# Input_Output.net
KiCad netlist of a schematic drawn in Altium Designer
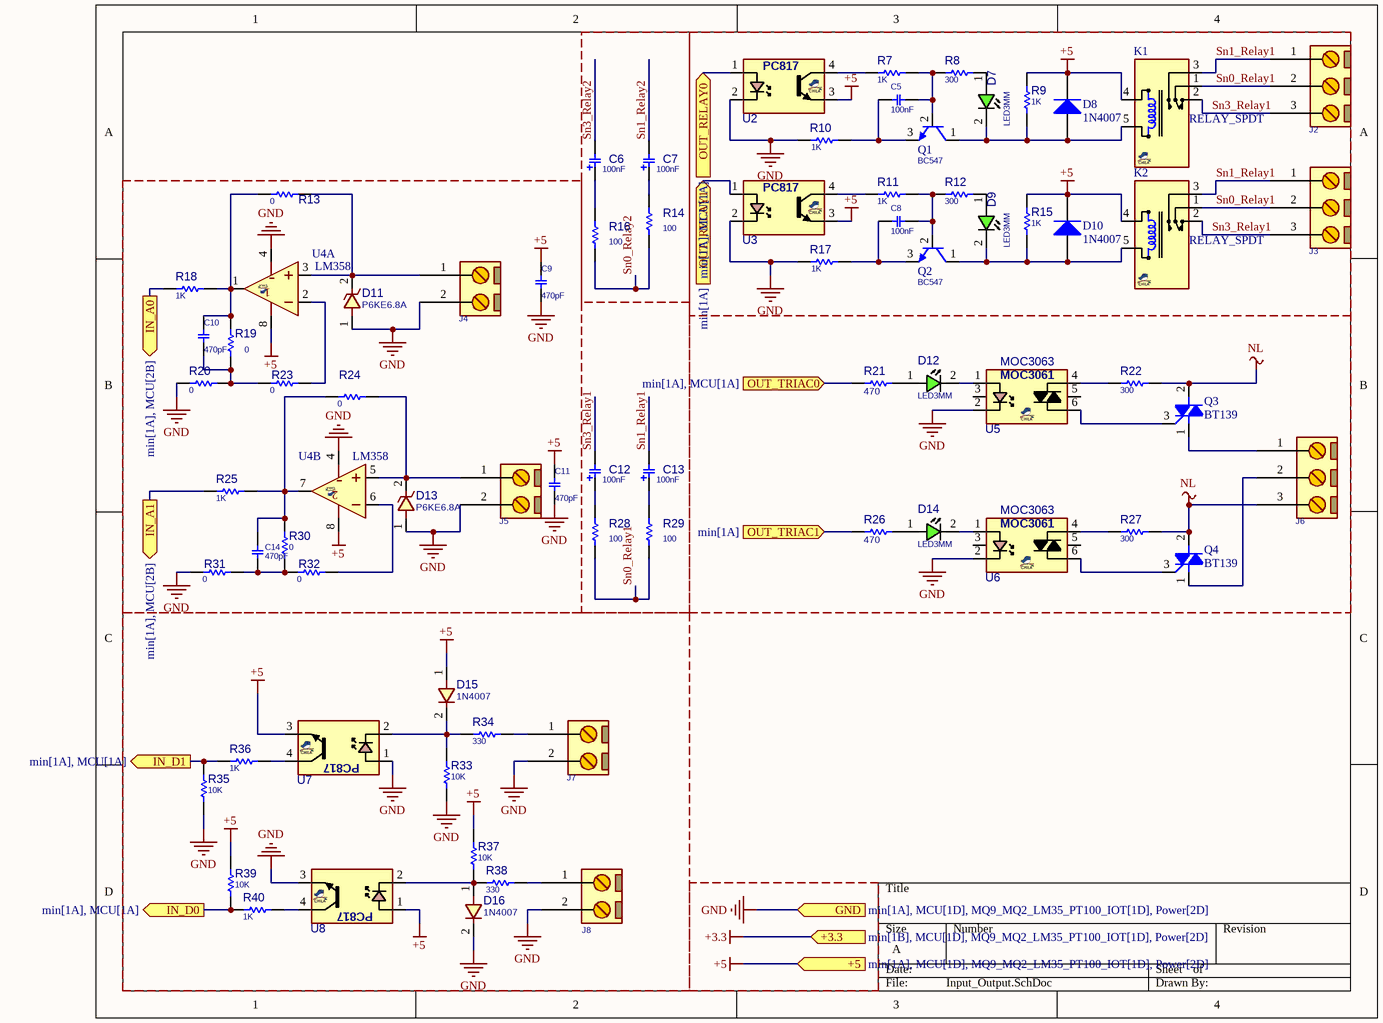
[diagram p0: Input_Output.SchDoc]

(export (version "E")
  (design (tool "Eeschema 10.0.6"))
  (components
    (comp (ref "C5")
      (value "100nF")
      (footprint "C_CERM_D3")
      (description "CAP, THD, CER MULTI LAYER,")
      (fields (field (name "MANF_P#") "MANF_PART#") (field (name "MANF") "MANF"))
      (libsource (lib "passive_thd") (part "CAP_THD_CER"))
    )
    (comp (ref "C6")
      (value "100nF")
      (footprint "C_FLM_10X5H7")
      (description "CAP, THD, FILM,")
      (fields (field (name "MANF_P#") "MANF_PART#") (field (name "MANF") "MANF"))
      (libsource (lib "passive_thd") (part "CAP_THD_FLM"))
    )
    (comp (ref "C7")
      (value "100nF")
      (footprint "C_FLM_10X5H7")
      (description "CAP, THD, FILM,")
      (fields (field (name "MANF_P#") "MANF_PART#") (field (name "MANF") "MANF"))
      (libsource (lib "passive_thd") (part "CAP_THD_FLM"))
    )
    (comp (ref "C8")
      (value "100nF")
      (footprint "C_CERM_D3")
      (description "CAP, THD, CER MULTI LAYER,")
      (fields (field (name "MANF_P#") "MANF_PART#") (field (name "MANF") "MANF"))
      (libsource (lib "passive_thd") (part "CAP_THD_CER"))
    )
    (comp (ref "C9")
      (value "470pF")
      (footprint "C_CERM_D3")
      (description "CAP, THD, CER MULTI LAYER,")
      (fields (field (name "MANF_P#") "MANF_PART#") (field (name "MANF") "MANF"))
      (libsource (lib "passive_thd") (part "CAP_THD_CER"))
    )
    (comp (ref "C10")
      (value "470pF")
      (footprint "C_CERM_D3")
      (description "CAP, THD, CER MULTI LAYER,")
      (fields (field (name "MANF_P#") "MANF_PART#") (field (name "MANF") "MANF"))
      (libsource (lib "passive_thd") (part "CAP_THD_CER"))
    )
    (comp (ref "C11")
      (value "470pF")
      (footprint "C_CERM_D3")
      (description "CAP, THD, CER MULTI LAYER,")
      (fields (field (name "MANF_P#") "MANF_PART#") (field (name "MANF") "MANF"))
      (libsource (lib "passive_thd") (part "CAP_THD_CER"))
    )
    (comp (ref "C12")
      (value "100nF")
      (footprint "C_FLM_10X5H7")
      (description "CAP, THD, FILM,")
      (fields (field (name "MANF_P#") "MANF_PART#") (field (name "MANF") "MANF"))
      (libsource (lib "passive_thd") (part "CAP_THD_FLM"))
    )
    (comp (ref "C13")
      (value "100nF")
      (footprint "C_FLM_10X5H7")
      (description "CAP, THD, FILM,")
      (fields (field (name "MANF_P#") "MANF_PART#") (field (name "MANF") "MANF"))
      (libsource (lib "passive_thd") (part "CAP_THD_FLM"))
    )
    (comp (ref "C14")
      (value "470pF")
      (footprint "C_CERM_D3")
      (description "CAP, THD, CER MULTI LAYER,")
      (fields (field (name "MANF_P#") "MANF_PART#") (field (name "MANF") "MANF"))
      (libsource (lib "passive_thd") (part "CAP_THD_CER"))
    )
    (comp (ref "D7")
      (value "LED3MM")
      (footprint "LED3MM")
      (description "LED, THD, 3MM, GREEN")
      (fields (field (name "MANF") "MANF") (field (name "MANF_P#") "MANF_PART#"))
      (libsource (lib "led(diode)") (part "LED_THD_3MM"))
    )
    (comp (ref "D8")
      (value "1N4007")
      (footprint "Diode 1n4007")
      (description "Diode")
      (fields (field (name "PUBLISHER") "Altium Limited"))
      (libsource (lib "Altium (2)") (part "Diode"))
    )
    (comp (ref "D9")
      (value "LED3MM")
      (footprint "LED3MM")
      (description "LED, THD, 3MM, GREEN")
      (fields (field (name "MANF") "MANF") (field (name "MANF_P#") "MANF_PART#"))
      (libsource (lib "led(diode)") (part "LED_THD_3MM"))
    )
    (comp (ref "D10")
      (value "1N4007")
      (footprint "Diode 1n4007")
      (description "Diode")
      (fields (field (name "PUBLISHER") "Altium Limited"))
      (libsource (lib "Altium (2)") (part "Diode"))
    )
    (comp (ref "D11")
      (value "P6KE6.8A")
      (footprint "D_AX04_DO41")
      (description "DIODE, ZENER, 0.2W, 15V")
      (fields (field (name "MANF") "Diodes") (field (name "MANF_P#") "ZENER15V"))
      (libsource (lib "diode") (part "DIODE_THD_ZENER"))
    )
    (comp (ref "D12")
      (value "LED3MM")
      (footprint "LED3MM")
      (description "LED, THD, 3MM, GREEN")
      (fields (field (name "MANF") "MANF") (field (name "MANF_P#") "MANF_PART#"))
      (libsource (lib "led(diode)") (part "LED_THD_3MM"))
    )
    (comp (ref "D13")
      (value "P6KE6.8A")
      (footprint "D_AX04_DO41")
      (description "DIODE, ZENER, 0.2W, 15V")
      (fields (field (name "MANF") "Diodes") (field (name "MANF_P#") "ZENER15V"))
      (libsource (lib "diode") (part "DIODE_THD_ZENER"))
    )
    (comp (ref "D14")
      (value "LED3MM")
      (footprint "LED3MM")
      (description "LED, THD, 3MM, GREEN")
      (fields (field (name "MANF") "MANF") (field (name "MANF_P#") "MANF_PART#"))
      (libsource (lib "led(diode)") (part "LED_THD_3MM"))
    )
    (comp (ref "D15")
      (value "1N4007")
      (footprint "D_AX04_DO41")
      (description "DIODE, GENERAL PURPOSE, 1000V/1A")
      (fields (field (name "MANF") "Diodes"))
      (libsource (lib "diode") (part "DIODE_THD_1N4007"))
    )
    (comp (ref "D16")
      (value "1N4007")
      (footprint "D_AX04_DO41")
      (description "DIODE, GENERAL PURPOSE, 1000V/1A")
      (fields (field (name "MANF") "Diodes"))
      (libsource (lib "diode") (part "DIODE_THD_1N4007"))
    )
    (comp (ref "J2")
      (value "CONN_GMSTB3")
      (footprint "GMSTB762_3")
      (description "CONN, PHOENIX MSTB, 5-G, 5.08mm pitch")
      (fields (field (name "MANF_P#") "GMSTB 2,5/3-G-7,62"))
      (libsource (lib "conn_terminalB") (part "CONN_GMSTB762_3"))
    )
    (comp (ref "J3")
      (value "CONN_GMSTB3")
      (footprint "GMSTB762_3")
      (description "CONN, PHOENIX MSTB, 5-G, 5.08mm pitch")
      (fields (field (name "MANF_P#") "GMSTB 2,5/3-G-7,62"))
      (libsource (lib "conn_terminalB") (part "CONN_GMSTB762_3"))
    )
    (comp (ref "J4")
      (value "CONN_GMSTB2")
      (footprint "GMSTB762_2")
      (description "CONN, PHOENIX GMSTB, 7.62mm pitch")
      (fields (field (name "MANF_P#") "GMSTB 2,5/2-G-7,62"))
      (libsource (lib "conn_terminalB") (part "CONN_GMSTB762_2"))
    )
    (comp (ref "J5")
      (value "CONN_GMSTB2")
      (footprint "GMSTB762_2")
      (description "CONN, PHOENIX GMSTB, 7.62mm pitch")
      (fields (field (name "MANF_P#") "GMSTB 2,5/2-G-7,62"))
      (libsource (lib "conn_terminalB") (part "CONN_GMSTB762_2"))
    )
    (comp (ref "J6")
      (value "CONN_GMSTB3")
      (footprint "GMSTB762_3")
      (description "CONN, PHOENIX MSTB, 5-G, 5.08mm pitch")
      (fields (field (name "MANF_P#") "GMSTB 2,5/3-G-7,62"))
      (libsource (lib "conn_terminalB") (part "CONN_GMSTB762_3"))
    )
    (comp (ref "J7")
      (value "CONN_GMSTB2")
      (footprint "GMSTB762_2")
      (description "CONN, PHOENIX GMSTB, 7.62mm pitch")
      (fields (field (name "MANF_P#") "GMSTB 2,5/2-G-7,62"))
      (libsource (lib "conn_terminalB") (part "CONN_GMSTB762_2"))
    )
    (comp (ref "J8")
      (value "CONN_GMSTB2")
      (footprint "GMSTB762_2")
      (description "CONN, PHOENIX GMSTB, 7.62mm pitch")
      (fields (field (name "MANF_P#") "GMSTB 2,5/2-G-7,62"))
      (libsource (lib "conn_terminalB") (part "CONN_GMSTB762_2"))
    )
    (comp (ref "K1")
      (value "RELAY_SPDT")
      (footprint "REL_SPDT_5_2216")
      (description "Relay, SPDT, 5P, 19X15mm, 240VAC/7A")
      (fields (field (name "MANF") "TIANBO") (field (name "MANF_P#") "HJR-3FF--12VDC"))
      (libsource (lib "relay") (part "RELAY_SPDT_5_2216_HJR-3FF"))
    )
    (comp (ref "K2")
      (value "RELAY_SPDT")
      (footprint "REL_SPDT_5_2216")
      (description "Relay, SPDT, 5P, 19X15mm, 240VAC/7A")
      (fields (field (name "MANF") "TIANBO") (field (name "MANF_P#") "HJR-3FF--12VDC"))
      (libsource (lib "relay") (part "RELAY_SPDT_5_2216_HJR-3FF"))
    )
    (comp (ref "Q1")
      (value "BC547")
      (footprint "TO92_3")
      (description "BJT, NPN, 45v, 0.1A, THD, TO92")
      (fields (field (name "MANF") "FAIRCHILD"))
      (libsource (lib "transistor_bjt") (part "NPN_BC547_TO92"))
    )
    (comp (ref "Q2")
      (value "BC547")
      (footprint "TO92_3")
      (description "BJT, NPN, 45v, 0.1A, THD, TO92")
      (fields (field (name "MANF") "FAIRCHILD"))
      (libsource (lib "transistor_bjt") (part "NPN_BC547_TO92"))
    )
    (comp (ref "Q3")
      (value "BT139")
      (footprint "TO220_3")
      (description "Triac, 600V, 4A, TO-220, Silicon Bidirectional Thyristor")
      (libsource (lib "triac_diac") (part "TRIAC"))
    )
    (comp (ref "Q4")
      (value "BT139")
      (footprint "TO220_3")
      (description "Triac, 600V, 4A, TO-220, Silicon Bidirectional Thyristor")
      (libsource (lib "triac_diac") (part "TRIAC"))
    )
    (comp (ref "R7")
      (value "1K")
      (footprint "R025W_AX_VER")
      (description "RESISTOR, THD")
      (fields (field (name "MANF_P#") "RK73H1ETTP4701F") (field (name "MANF") "KOA SPEER"))
      (libsource (lib "passive_thd") (part "RES_THD"))
    )
    (comp (ref "R8")
      (value "300")
      (footprint "R025W_AX_VER")
      (description "RESISTOR, THD")
      (fields (field (name "MANF_P#") "RK73H1ETTP4701F") (field (name "MANF") "KOA SPEER"))
      (libsource (lib "passive_thd") (part "RES_THD"))
    )
    (comp (ref "R9")
      (value "1K")
      (footprint "R025W_AX_VER")
      (description "RESISTOR, THD")
      (fields (field (name "MANF_P#") "RK73H1ETTP4701F") (field (name "MANF") "KOA SPEER"))
      (libsource (lib "passive_thd") (part "RES_THD"))
    )
    (comp (ref "R10")
      (value "1K")
      (footprint "R025W_AX_VER")
      (description "RESISTOR, THD")
      (fields (field (name "MANF_P#") "RK73H1ETTP4701F") (field (name "MANF") "KOA SPEER"))
      (libsource (lib "passive_thd") (part "RES_THD"))
    )
    (comp (ref "R11")
      (value "1K")
      (footprint "R025W_AX_VER")
      (description "RESISTOR, THD")
      (fields (field (name "MANF_P#") "RK73H1ETTP4701F") (field (name "MANF") "KOA SPEER"))
      (libsource (lib "passive_thd") (part "RES_THD"))
    )
    (comp (ref "R12")
      (value "300")
      (footprint "R025W_AX_VER")
      (description "RESISTOR, THD")
      (fields (field (name "MANF_P#") "RK73H1ETTP4701F") (field (name "MANF") "KOA SPEER"))
      (libsource (lib "passive_thd") (part "RES_THD"))
    )
    (comp (ref "R13")
      (value "0")
      (footprint "R0125W_AX03")
      (description "RESISTOR, THD")
      (fields (field (name "MANF_P#") "RK73H1ETTP4701F") (field (name "MANF") "KOA SPEER"))
      (libsource (lib "passive_thd") (part "RES_THD"))
    )
    (comp (ref "R14")
      (value "100")
      (footprint "R025W_AX_VER")
      (description "RESISTOR, THD")
      (fields (field (name "MANF_P#") "RK73H1ETTP4701F") (field (name "MANF") "KOA SPEER"))
      (libsource (lib "passive_thd") (part "RES_THD"))
    )
    (comp (ref "R15")
      (value "1K")
      (footprint "R025W_AX_VER")
      (description "RESISTOR, THD")
      (fields (field (name "MANF_P#") "RK73H1ETTP4701F") (field (name "MANF") "KOA SPEER"))
      (libsource (lib "passive_thd") (part "RES_THD"))
    )
    (comp (ref "R16")
      (value "100")
      (footprint "R025W_AX_VER")
      (description "RESISTOR, THD")
      (fields (field (name "MANF_P#") "RK73H1ETTP4701F") (field (name "MANF") "KOA SPEER"))
      (libsource (lib "passive_thd") (part "RES_THD"))
    )
    (comp (ref "R17")
      (value "1K")
      (footprint "R025W_AX_VER")
      (description "RESISTOR, THD")
      (fields (field (name "MANF_P#") "RK73H1ETTP4701F") (field (name "MANF") "KOA SPEER"))
      (libsource (lib "passive_thd") (part "RES_THD"))
    )
    (comp (ref "R18")
      (value "1K")
      (footprint "R0125W_AX03")
      (description "RESISTOR, THD")
      (fields (field (name "MANF_P#") "RK73H1ETTP4701F") (field (name "MANF") "KOA SPEER"))
      (libsource (lib "passive_thd") (part "RES_THD"))
    )
    (comp (ref "R19")
      (value "0")
      (footprint "R0125W_AX03")
      (description "RESISTOR, THD")
      (fields (field (name "MANF_P#") "RK73H1ETTP4701F") (field (name "MANF") "KOA SPEER"))
      (libsource (lib "passive_thd") (part "RES_THD"))
    )
    (comp (ref "R20")
      (value "0")
      (footprint "R0125W_AX03")
      (description "RESISTOR, THD")
      (fields (field (name "MANF_P#") "RK73H1ETTP4701F") (field (name "MANF") "KOA SPEER"))
      (libsource (lib "passive_thd") (part "RES_THD"))
    )
    (comp (ref "R21")
      (value "470")
      (footprint "R1206")
      (description "RESISTOR, SMD")
      (libsource (lib "passive_smd") (part "RES_SMD"))
    )
    (comp (ref "R22")
      (value "300")
      (footprint "R025W_AX_VER")
      (description "RESISTOR, THD")
      (fields (field (name "MANF_P#") "RK73H1ETTP4701F") (field (name "MANF") "KOA SPEER"))
      (libsource (lib "passive_thd") (part "RES_THD"))
    )
    (comp (ref "R23")
      (value "0")
      (footprint "R0125W_AX03")
      (description "RESISTOR, THD")
      (fields (field (name "MANF_P#") "RK73H1ETTP4701F") (field (name "MANF") "KOA SPEER"))
      (libsource (lib "passive_thd") (part "RES_THD"))
    )
    (comp (ref "R24")
      (value "0")
      (footprint "R0125W_AX03")
      (description "RESISTOR, THD")
      (fields (field (name "MANF_P#") "RK73H1ETTP4701F") (field (name "MANF") "KOA SPEER"))
      (libsource (lib "passive_thd") (part "RES_THD"))
    )
    (comp (ref "R25")
      (value "1K")
      (footprint "R0125W_AX03")
      (description "RESISTOR, THD")
      (fields (field (name "MANF_P#") "RK73H1ETTP4701F") (field (name "MANF") "KOA SPEER"))
      (libsource (lib "passive_thd") (part "RES_THD"))
    )
    (comp (ref "R26")
      (value "470")
      (footprint "R1206")
      (description "RESISTOR, SMD")
      (libsource (lib "passive_smd") (part "RES_SMD"))
    )
    (comp (ref "R27")
      (value "300")
      (footprint "R025W_AX_VER")
      (description "RESISTOR, THD")
      (fields (field (name "MANF_P#") "RK73H1ETTP4701F") (field (name "MANF") "KOA SPEER"))
      (libsource (lib "passive_thd") (part "RES_THD"))
    )
    (comp (ref "R28")
      (value "100")
      (footprint "R025W_AX_VER")
      (description "RESISTOR, THD")
      (fields (field (name "MANF_P#") "RK73H1ETTP4701F") (field (name "MANF") "KOA SPEER"))
      (libsource (lib "passive_thd") (part "RES_THD"))
    )
    (comp (ref "R29")
      (value "100")
      (footprint "R025W_AX_VER")
      (description "RESISTOR, THD")
      (fields (field (name "MANF_P#") "RK73H1ETTP4701F") (field (name "MANF") "KOA SPEER"))
      (libsource (lib "passive_thd") (part "RES_THD"))
    )
    (comp (ref "R30")
      (value "0")
      (footprint "R0125W_AX03")
      (description "RESISTOR, THD")
      (fields (field (name "MANF_P#") "RK73H1ETTP4701F") (field (name "MANF") "KOA SPEER"))
      (libsource (lib "passive_thd") (part "RES_THD"))
    )
    (comp (ref "R31")
      (value "0")
      (footprint "R0125W_AX03")
      (description "RESISTOR, THD")
      (fields (field (name "MANF_P#") "RK73H1ETTP4701F") (field (name "MANF") "KOA SPEER"))
      (libsource (lib "passive_thd") (part "RES_THD"))
    )
    (comp (ref "R32")
      (value "0")
      (footprint "R0125W_AX03")
      (description "RESISTOR, THD")
      (fields (field (name "MANF_P#") "RK73H1ETTP4701F") (field (name "MANF") "KOA SPEER"))
      (libsource (lib "passive_thd") (part "RES_THD"))
    )
    (comp (ref "R33")
      (value "10K")
      (footprint "R0125W_AX03")
      (description "RESISTOR, THD")
      (fields (field (name "MANF_P#") "RK73H1ETTP4701F") (field (name "MANF") "KOA SPEER"))
      (libsource (lib "passive_thd") (part "RES_THD"))
    )
    (comp (ref "R34")
      (value "330")
      (footprint "R0125W_AX03")
      (description "RESISTOR, THD")
      (fields (field (name "MANF_P#") "RK73H1ETTP4701F") (field (name "MANF") "KOA SPEER"))
      (libsource (lib "passive_thd") (part "RES_THD"))
    )
    (comp (ref "R35")
      (value "10K")
      (footprint "R0125W_AX03")
      (description "RESISTOR, THD")
      (fields (field (name "MANF_P#") "RK73H1ETTP4701F") (field (name "MANF") "KOA SPEER"))
      (libsource (lib "passive_thd") (part "RES_THD"))
    )
    (comp (ref "R36")
      (value "1K")
      (footprint "R0125W_AX03")
      (description "RESISTOR, THD")
      (fields (field (name "MANF_P#") "RK73H1ETTP4701F") (field (name "MANF") "KOA SPEER"))
      (libsource (lib "passive_thd") (part "RES_THD"))
    )
    (comp (ref "R37")
      (value "10K")
      (footprint "R0125W_AX03")
      (description "RESISTOR, THD")
      (fields (field (name "MANF_P#") "RK73H1ETTP4701F") (field (name "MANF") "KOA SPEER"))
      (libsource (lib "passive_thd") (part "RES_THD"))
    )
    (comp (ref "R38")
      (value "330")
      (footprint "R0125W_AX03")
      (description "RESISTOR, THD")
      (fields (field (name "MANF_P#") "RK73H1ETTP4701F") (field (name "MANF") "KOA SPEER"))
      (libsource (lib "passive_thd") (part "RES_THD"))
    )
    (comp (ref "R39")
      (value "10K")
      (footprint "R0125W_AX03")
      (description "RESISTOR, THD")
      (fields (field (name "MANF_P#") "RK73H1ETTP4701F") (field (name "MANF") "KOA SPEER"))
      (libsource (lib "passive_thd") (part "RES_THD"))
    )
    (comp (ref "R40")
      (value "1K")
      (footprint "R0125W_AX03")
      (description "RESISTOR, THD")
      (fields (field (name "MANF_P#") "RK73H1ETTP4701F") (field (name "MANF") "KOA SPEER"))
      (libsource (lib "passive_thd") (part "RES_THD"))
    )
    (comp (ref "U2")
      (value "PC817")
      (footprint "DIP_4")
      (description "OPTOCOUPLER, TRANSISTOR, 4PIN")
      (fields (field (name "MANF") "SHARP"))
      (libsource (lib "") (part "OPTC_TR4P_PC817_1"))
    )
    (comp (ref "U3")
      (value "PC817")
      (footprint "DIP_4")
      (description "OPTOCOUPLER, TRANSISTOR, 4PIN")
      (fields (field (name "MANF") "SHARP"))
      (libsource (lib "") (part "OPTC_TR4P_PC817_1"))
    )
    (comp (ref "U4")
      (value "LM358")
      (footprint "DIP_8")
      (description "AMP, Dual, Low-Power")
      (fields (field (name "MANF") "Texas Instruments, Fairchild") (field (name "MANF_P#") "LM358AN"))
      (libsource (lib "amp") (part "LM358_DIP8"))
    )
    (comp (ref "U5")
      (value "MOC3063")
      (footprint "DIP_6")
      (description "OPTOTRIAC, 600v/1A, 6v In")
      (fields (field (name "MANF_P#") "MOC3061"))
      (libsource (lib "optocoupler") (part "OPT_TRIAC6P_MOC3061"))
    )
    (comp (ref "U6")
      (value "MOC3063")
      (footprint "DIP_6")
      (description "OPTOTRIAC, 600v/1A, 6v In")
      (fields (field (name "MANF_P#") "MOC3061"))
      (libsource (lib "optocoupler") (part "OPT_TRIAC6P_MOC3061"))
    )
    (comp (ref "U7")
      (value "PC817")
      (footprint "DIP_4")
      (description "OPTOCOUPLER, TRANSISTOR, 4PIN")
      (fields (field (name "MANF") "SHARP"))
      (libsource (lib "optocoupler") (part "OPTC_TR4P_PC817"))
    )
    (comp (ref "U8")
      (value "PC817")
      (footprint "DIP_4")
      (description "OPTOCOUPLER, TRANSISTOR, 4PIN")
      (fields (field (name "MANF") "SHARP"))
      (libsource (lib "optocoupler") (part "OPTC_TR4P_PC817"))
    )
  )
  (nets
    (net (code "2") (name "+5") (class "Default")
      (node (ref "C11") (pin "2") (pinfunction "2_2") (pintype "passive"))
      (node (ref "C9") (pin "2") (pinfunction "2_2") (pintype "passive"))
      (node (ref "D10") (pin "2") (pinfunction "K_2") (pintype "passive"))
      (node (ref "D15") (pin "1") (pinfunction "1_1") (pintype "passive"))
      (node (ref "D8") (pin "2") (pinfunction "K_2") (pintype "passive"))
      (node (ref "K1") (pin "4") (pinfunction "T1_4") (pintype "passive"))
      (node (ref "K2") (pin "4") (pinfunction "T1_4") (pintype "passive"))
      (node (ref "R15") (pin "1") (pinfunction "1_1") (pintype "passive"))
      (node (ref "R37") (pin "2") (pinfunction "2_2") (pintype "passive"))
      (node (ref "R39") (pin "2") (pinfunction "2_2") (pintype "passive"))
      (node (ref "R9") (pin "1") (pinfunction "1_1") (pintype "passive"))
      (node (ref "U2") (pin "3") (pinfunction "E_3") (pintype "passive"))
      (node (ref "U3") (pin "3") (pinfunction "E_3") (pintype "passive"))
      (node (ref "U4") (pin "8") (pinfunction "V+_8") (pintype "passive"))
      (node (ref "U7") (pin "3") (pinfunction "E_3") (pintype "passive"))
      (node (ref "U8") (pin "1") (pinfunction "A_1") (pintype "passive"))
    )
    (net (code "3") (name "/IN_A0") (class "Default")
      (node (ref "R18") (pin "2") (pinfunction "2_2") (pintype "passive"))
    )
    (net (code "4") (name "/IN_A1") (class "Default")
      (node (ref "R25") (pin "2") (pinfunction "2_2") (pintype "passive"))
    )
    (net (code "5") (name "/IN_D0") (class "Default")
      (node (ref "R39") (pin "1") (pinfunction "1_1") (pintype "passive"))
      (node (ref "R40") (pin "1") (pinfunction "1_1") (pintype "passive"))
    )
    (net (code "6") (name "/IN_D1") (class "Default")
      (node (ref "R35") (pin "1") (pinfunction "1_1") (pintype "passive"))
      (node (ref "R36") (pin "1") (pinfunction "1_1") (pintype "passive"))
    )
    (net (code "7") (name "/OUT_RELAY0") (class "Default")
      (node (ref "U2") (pin "1") (pinfunction "A_1") (pintype "passive"))
    )
    (net (code "8") (name "/OUT_RELAY1") (class "Default")
      (node (ref "U3") (pin "1") (pinfunction "A_1") (pintype "passive"))
    )
    (net (code "9") (name "/OUT_TRIAC0") (class "Default")
      (node (ref "R21") (pin "2") (pinfunction "2_2") (pintype "passive"))
    )
    (net (code "10") (name "/OUT_TRIAC1") (class "Default")
      (node (ref "R26") (pin "2") (pinfunction "2_2") (pintype "passive"))
    )
    (net (code "11") (name "/Sn0_Relay1") (class "Default")
      (node (ref "J2") (pin "2") (pinfunction "2_2") (pintype "passive"))
      (node (ref "J3") (pin "2") (pinfunction "2_2") (pintype "passive"))
      (node (ref "K1") (pin "1") (pinfunction "COM_1") (pintype "passive"))
      (node (ref "K2") (pin "1") (pinfunction "COM_1") (pintype "passive"))
      (node (ref "R28") (pin "1") (pinfunction "1_1") (pintype "passive"))
      (node (ref "R29") (pin "1") (pinfunction "1_1") (pintype "passive"))
    )
    (net (code "12") (name "/Sn0_Relay2") (class "Default")
      (node (ref "R14") (pin "1") (pinfunction "1_1") (pintype "passive"))
      (node (ref "R16") (pin "1") (pinfunction "1_1") (pintype "passive"))
    )
    (net (code "13") (name "/Sn1_Relay1") (class "Default")
      (node (ref "C13") (pin "2") (pinfunction "2_2") (pintype "passive"))
      (node (ref "J2") (pin "1") (pinfunction "1_1") (pintype "passive"))
      (node (ref "J3") (pin "1") (pinfunction "1_1") (pintype "passive"))
      (node (ref "K1") (pin "3") (pinfunction "NO_3") (pintype "passive"))
      (node (ref "K2") (pin "3") (pinfunction "NO_3") (pintype "passive"))
    )
    (net (code "14") (name "/Sn1_Relay2") (class "Default")
      (node (ref "C7") (pin "2") (pinfunction "2_2") (pintype "passive"))
    )
    (net (code "15") (name "/Sn3_Relay1") (class "Default")
      (node (ref "C12") (pin "2") (pinfunction "2_2") (pintype "passive"))
      (node (ref "J2") (pin "3") (pinfunction "3_3") (pintype "passive"))
      (node (ref "J3") (pin "3") (pinfunction "3_3") (pintype "passive"))
      (node (ref "K1") (pin "2") (pinfunction "NC_2") (pintype "passive"))
      (node (ref "K2") (pin "2") (pinfunction "NC_2") (pintype "passive"))
    )
    (net (code "16") (name "/Sn3_Relay2") (class "Default")
      (node (ref "C6") (pin "2") (pinfunction "2_2") (pintype "passive"))
    )
    (net (code "17") (name "GND") (class "Default")
      (node (ref "C11") (pin "1") (pinfunction "1_1") (pintype "passive"))
      (node (ref "C9") (pin "1") (pinfunction "1_1") (pintype "passive"))
      (node (ref "D11") (pin "1") (pinfunction "1_1") (pintype "passive"))
      (node (ref "D13") (pin "1") (pinfunction "1_1") (pintype "passive"))
      (node (ref "D16") (pin "2") (pinfunction "2_2") (pintype "passive"))
      (node (ref "J4") (pin "2") (pinfunction "2_2") (pintype "passive"))
      (node (ref "J5") (pin "2") (pinfunction "2_2") (pintype "passive"))
      (node (ref "J7") (pin "2") (pinfunction "2_2") (pintype "passive"))
      (node (ref "J8") (pin "2") (pinfunction "2_2") (pintype "passive"))
      (node (ref "R10") (pin "2") (pinfunction "2_2") (pintype "passive"))
      (node (ref "R17") (pin "2") (pinfunction "2_2") (pintype "passive"))
      (node (ref "R20") (pin "2") (pinfunction "2_2") (pintype "passive"))
      (node (ref "R31") (pin "2") (pinfunction "2_2") (pintype "passive"))
      (node (ref "R33") (pin "2") (pinfunction "2_2") (pintype "passive"))
      (node (ref "R35") (pin "2") (pinfunction "2_2") (pintype "passive"))
      (node (ref "U2") (pin "2") (pinfunction "K_2") (pintype "passive"))
      (node (ref "U3") (pin "2") (pinfunction "K_2") (pintype "passive"))
      (node (ref "U4") (pin "4") (pinfunction "V-_4") (pintype "passive"))
      (node (ref "U5") (pin "2") (pinfunction "K_2") (pintype "passive"))
      (node (ref "U6") (pin "2") (pinfunction "K_2") (pintype "passive"))
      (node (ref "U7") (pin "1") (pinfunction "A_1") (pintype "passive"))
      (node (ref "U8") (pin "3") (pinfunction "E_3") (pintype "passive"))
    )
    (net (code "18") (name "NL") (class "Default")
      (node (ref "J6") (pin "3") (pinfunction "3_3") (pintype "passive"))
      (node (ref "Q3") (pin "2") (pinfunction "T2_2") (pintype "passive"))
      (node (ref "Q4") (pin "2") (pinfunction "T2_2") (pintype "passive"))
      (node (ref "R22") (pin "2") (pinfunction "2_2") (pintype "passive"))
      (node (ref "R27") (pin "2") (pinfunction "2_2") (pintype "passive"))
    )
    (net (code "19") (name "Net-(C6-Pad1)") (class "Default")
      (node (ref "C6") (pin "1") (pinfunction "1_1") (pintype "passive"))
      (node (ref "R16") (pin "2") (pinfunction "2_2") (pintype "passive"))
    )
    (net (code "20") (name "Net-(C7-Pad1)") (class "Default")
      (node (ref "C7") (pin "1") (pinfunction "1_1") (pintype "passive"))
      (node (ref "R14") (pin "2") (pinfunction "2_2") (pintype "passive"))
    )
    (net (code "21") (name "Net-(C10-Pad1)") (class "Default")
      (node (ref "C10") (pin "1") (pinfunction "1_1") (pintype "passive"))
      (node (ref "R19") (pin "2") (pinfunction "2_2") (pintype "passive"))
      (node (ref "R20") (pin "1") (pinfunction "1_1") (pintype "passive"))
      (node (ref "R23") (pin "1") (pinfunction "1_1") (pintype "passive"))
    )
    (net (code "22") (name "Net-(C12-Pad1)") (class "Default")
      (node (ref "C12") (pin "1") (pinfunction "1_1") (pintype "passive"))
      (node (ref "R28") (pin "2") (pinfunction "2_2") (pintype "passive"))
    )
    (net (code "23") (name "Net-(C13-Pad1)") (class "Default")
      (node (ref "C13") (pin "1") (pinfunction "1_1") (pintype "passive"))
      (node (ref "R29") (pin "2") (pinfunction "2_2") (pintype "passive"))
    )
    (net (code "24") (name "Net-(C14-Pad1)") (class "Default")
      (node (ref "C14") (pin "1") (pinfunction "1_1") (pintype "passive"))
      (node (ref "R30") (pin "1") (pinfunction "1_1") (pintype "passive"))
      (node (ref "R31") (pin "1") (pinfunction "1_1") (pintype "passive"))
      (node (ref "R32") (pin "1") (pinfunction "1_1") (pintype "passive"))
    )
    (net (code "25") (name "Net-(D7-ANODE)") (class "Default")
      (node (ref "D7") (pin "1") (pinfunction "ANODE_1") (pintype "passive"))
      (node (ref "R8") (pin "2") (pinfunction "2_2") (pintype "passive"))
    )
    (net (code "26") (name "Net-(D7-CATHODE)") (class "Default")
      (node (ref "D7") (pin "2") (pinfunction "CATHODE_2") (pintype "passive"))
      (node (ref "D8") (pin "1") (pinfunction "A_1") (pintype "passive"))
      (node (ref "K1") (pin "5") (pinfunction "T2_5") (pintype "passive"))
      (node (ref "Q1") (pin "1") (pinfunction "C_1") (pintype "passive"))
      (node (ref "R9") (pin "2") (pinfunction "2_2") (pintype "passive"))
    )
    (net (code "27") (name "Net-(D9-ANODE)") (class "Default")
      (node (ref "D9") (pin "1") (pinfunction "ANODE_1") (pintype "passive"))
      (node (ref "R12") (pin "2") (pinfunction "2_2") (pintype "passive"))
    )
    (net (code "28") (name "Net-(D10-A)") (class "Default")
      (node (ref "D10") (pin "1") (pinfunction "A_1") (pintype "passive"))
      (node (ref "D9") (pin "2") (pinfunction "CATHODE_2") (pintype "passive"))
      (node (ref "K2") (pin "5") (pinfunction "T2_5") (pintype "passive"))
      (node (ref "Q2") (pin "1") (pinfunction "C_1") (pintype "passive"))
      (node (ref "R15") (pin "2") (pinfunction "2_2") (pintype "passive"))
    )
    (net (code "29") (name "Net-(D12-ANODE)") (class "Default")
      (node (ref "D12") (pin "1") (pinfunction "ANODE_1") (pintype "passive"))
      (node (ref "R21") (pin "1") (pinfunction "1_1") (pintype "passive"))
    )
    (net (code "30") (name "Net-(D12-CATHODE)") (class "Default")
      (node (ref "D12") (pin "2") (pinfunction "CATHODE_2") (pintype "passive"))
      (node (ref "U5") (pin "1") (pinfunction "A_1") (pintype "passive"))
    )
    (net (code "31") (name "Net-(D14-ANODE)") (class "Default")
      (node (ref "D14") (pin "1") (pinfunction "ANODE_1") (pintype "passive"))
      (node (ref "R26") (pin "1") (pinfunction "1_1") (pintype "passive"))
    )
    (net (code "32") (name "Net-(D14-CATHODE)") (class "Default")
      (node (ref "D14") (pin "2") (pinfunction "CATHODE_2") (pintype "passive"))
      (node (ref "U6") (pin "1") (pinfunction "A_1") (pintype "passive"))
    )
    (net (code "33") (name "Net-(J7-Pad1)") (class "Default")
      (node (ref "J7") (pin "1") (pinfunction "1_1") (pintype "passive"))
      (node (ref "R34") (pin "2") (pinfunction "2_2") (pintype "passive"))
    )
    (net (code "34") (name "Net-(J8-Pad1)") (class "Default")
      (node (ref "J8") (pin "1") (pinfunction "1_1") (pintype "passive"))
      (node (ref "R38") (pin "2") (pinfunction "2_2") (pintype "passive"))
    )
    (net (code "35") (name "Net-(Q1-B)") (class "Default")
      (node (ref "C5") (pin "1") (pinfunction "1_1") (pintype "passive"))
      (node (ref "Q1") (pin "2") (pinfunction "B_2") (pintype "passive"))
      (node (ref "R7") (pin "1") (pinfunction "1_1") (pintype "passive"))
      (node (ref "R8") (pin "1") (pinfunction "1_1") (pintype "passive"))
    )
    (net (code "36") (name "Net-(Q1-E)") (class "Default")
      (node (ref "C5") (pin "2") (pinfunction "2_2") (pintype "passive"))
      (node (ref "Q1") (pin "3") (pinfunction "E_3") (pintype "passive"))
      (node (ref "R10") (pin "1") (pinfunction "1_1") (pintype "passive"))
    )
    (net (code "37") (name "Net-(Q2-B)") (class "Default")
      (node (ref "C8") (pin "1") (pinfunction "1_1") (pintype "passive"))
      (node (ref "Q2") (pin "2") (pinfunction "B_2") (pintype "passive"))
      (node (ref "R11") (pin "1") (pinfunction "1_1") (pintype "passive"))
      (node (ref "R12") (pin "1") (pinfunction "1_1") (pintype "passive"))
    )
    (net (code "38") (name "Net-(Q2-E)") (class "Default")
      (node (ref "C8") (pin "2") (pinfunction "2_2") (pintype "passive"))
      (node (ref "Q2") (pin "3") (pinfunction "E_3") (pintype "passive"))
      (node (ref "R17") (pin "1") (pinfunction "1_1") (pintype "passive"))
    )
    (net (code "39") (name "Net-(Q3-G)") (class "Default")
      (node (ref "Q3") (pin "3") (pinfunction "G_3") (pintype "passive"))
      (node (ref "U5") (pin "6") (pinfunction "A/K_6") (pintype "passive"))
    )
    (net (code "40") (name "Net-(Q3-T1)") (class "Default")
      (node (ref "J6") (pin "1") (pinfunction "1_1") (pintype "passive"))
      (node (ref "Q3") (pin "1") (pinfunction "T1_1") (pintype "passive"))
    )
    (net (code "41") (name "Net-(Q4-G)") (class "Default")
      (node (ref "Q4") (pin "3") (pinfunction "G_3") (pintype "passive"))
      (node (ref "U6") (pin "6") (pinfunction "A/K_6") (pintype "passive"))
    )
    (net (code "42") (name "Net-(Q4-T1)") (class "Default")
      (node (ref "J6") (pin "2") (pinfunction "2_2") (pintype "passive"))
      (node (ref "Q4") (pin "1") (pinfunction "T1_1") (pintype "passive"))
    )
    (net (code "43") (name "Net-(R22-Pad1)") (class "Default")
      (node (ref "R22") (pin "1") (pinfunction "1_1") (pintype "passive"))
      (node (ref "U5") (pin "4") (pinfunction "A/K_4") (pintype "passive"))
    )
    (net (code "44") (name "Net-(R27-Pad1)") (class "Default")
      (node (ref "R27") (pin "1") (pinfunction "1_1") (pintype "passive"))
      (node (ref "U6") (pin "4") (pinfunction "A/K_4") (pintype "passive"))
    )
    (net (code "45") (name "Net-(U2-C)") (class "Default")
      (node (ref "R7") (pin "2") (pinfunction "2_2") (pintype "passive"))
      (node (ref "U2") (pin "4") (pinfunction "C_4") (pintype "passive"))
    )
    (net (code "46") (name "Net-(U3-C)") (class "Default")
      (node (ref "R11") (pin "2") (pinfunction "2_2") (pintype "passive"))
      (node (ref "U3") (pin "4") (pinfunction "C_4") (pintype "passive"))
    )
    (net (code "47") (name "Net-(U4A-IN+)") (class "Default")
      (node (ref "D11") (pin "2") (pinfunction "2_2") (pintype "passive"))
      (node (ref "J4") (pin "1") (pinfunction "1_1") (pintype "passive"))
      (node (ref "R13") (pin "1") (pinfunction "1_1") (pintype "passive"))
      (node (ref "U4") (pin "3") (pinfunction "IN+_3") (pintype "passive"))
    )
    (net (code "48") (name "Net-(U4A-IN-)") (class "Default")
      (node (ref "R23") (pin "2") (pinfunction "2_2") (pintype "passive"))
      (node (ref "U4") (pin "2") (pinfunction "IN-_2") (pintype "passive"))
    )
    (net (code "49") (name "Net-(U4A-OUT)") (class "Default")
      (node (ref "C10") (pin "2") (pinfunction "2_2") (pintype "passive"))
      (node (ref "R13") (pin "2") (pinfunction "2_2") (pintype "passive"))
      (node (ref "R18") (pin "1") (pinfunction "1_1") (pintype "passive"))
      (node (ref "R19") (pin "1") (pinfunction "1_1") (pintype "passive"))
      (node (ref "U4") (pin "1") (pinfunction "OUT_1") (pintype "passive"))
    )
    (net (code "50") (name "Net-(U4B-IN+)") (class "Default")
      (node (ref "D13") (pin "2") (pinfunction "2_2") (pintype "passive"))
      (node (ref "J5") (pin "1") (pinfunction "1_1") (pintype "passive"))
      (node (ref "R24") (pin "2") (pinfunction "2_2") (pintype "passive"))
      (node (ref "U4") (pin "5") (pinfunction "IN+_5") (pintype "passive"))
    )
    (net (code "51") (name "Net-(U4B-IN-)") (class "Default")
      (node (ref "R32") (pin "2") (pinfunction "2_2") (pintype "passive"))
      (node (ref "U4") (pin "6") (pinfunction "IN-_6") (pintype "passive"))
    )
    (net (code "52") (name "Net-(U4B-OUT)") (class "Default")
      (node (ref "C14") (pin "2") (pinfunction "2_2") (pintype "passive"))
      (node (ref "R24") (pin "1") (pinfunction "1_1") (pintype "passive"))
      (node (ref "R25") (pin "1") (pinfunction "1_1") (pintype "passive"))
      (node (ref "R30") (pin "2") (pinfunction "2_2") (pintype "passive"))
      (node (ref "U4") (pin "7") (pinfunction "OUT_7") (pintype "passive"))
    )
    (net (code "53") (name "Net-(U7-C)") (class "Default")
      (node (ref "R36") (pin "2") (pinfunction "2_2") (pintype "passive"))
      (node (ref "U7") (pin "4") (pinfunction "C_4") (pintype "passive"))
    )
    (net (code "54") (name "Net-(U7-K)") (class "Default")
      (node (ref "D15") (pin "2") (pinfunction "2_2") (pintype "passive"))
      (node (ref "R33") (pin "1") (pinfunction "1_1") (pintype "passive"))
      (node (ref "R34") (pin "1") (pinfunction "1_1") (pintype "passive"))
      (node (ref "U7") (pin "2") (pinfunction "K_2") (pintype "passive"))
    )
    (net (code "55") (name "Net-(U8-C)") (class "Default")
      (node (ref "R40") (pin "2") (pinfunction "2_2") (pintype "passive"))
      (node (ref "U8") (pin "4") (pinfunction "C_4") (pintype "passive"))
    )
    (net (code "56") (name "Net-(U8-K)") (class "Default")
      (node (ref "D16") (pin "1") (pinfunction "1_1") (pintype "passive"))
      (node (ref "R37") (pin "1") (pinfunction "1_1") (pintype "passive"))
      (node (ref "R38") (pin "1") (pinfunction "1_1") (pintype "passive"))
      (node (ref "U8") (pin "2") (pinfunction "K_2") (pintype "passive"))
    )
    (net (code "57") (name "unconnected-(U5-NC-Pad3)") (class "Default")
      (node (ref "U5") (pin "3") (pinfunction "NC_3") (pintype "passive"))
    )
    (net (code "58") (name "unconnected-(U5-NC-Pad5)") (class "Default")
      (node (ref "U5") (pin "5") (pinfunction "NC_5") (pintype "passive"))
    )
    (net (code "59") (name "unconnected-(U6-NC-Pad3)") (class "Default")
      (node (ref "U6") (pin "3") (pinfunction "NC_3") (pintype "passive"))
    )
    (net (code "60") (name "unconnected-(U6-NC-Pad5)") (class "Default")
      (node (ref "U6") (pin "5") (pinfunction "NC_5") (pintype "passive"))
    )
  )
)
